# simple-board.net
KiCad netlist of a schematic drawn in EAGLE
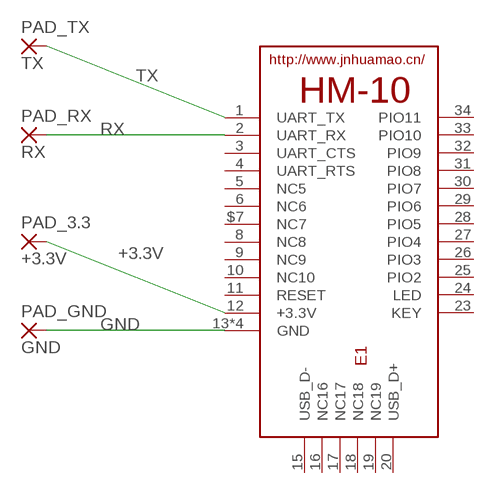
[diagram p0: schematic, sheet 1]

(export (version "E")
  (design (tool "Eeschema 10.0.6"))
  (components
    (comp (ref "E1")
      (value "HM-10-BOARD")
      (footprint "eagle-import:26.9X13X2.2_BOARD")
      (libsource (lib "eagle-import") (part "HM-10-BOARD"))
    )
    (comp (ref "PAD_3.3")
      (value "+3.3V")
      (footprint "eagle-import:1,6_0,8")
      (libsource (lib "eagle-import") (part "1,6/0,8"))
    )
    (comp (ref "PAD_GND")
      (value "GND")
      (footprint "eagle-import:1,6_0,8")
      (libsource (lib "eagle-import") (part "1,6/0,8"))
    )
    (comp (ref "PAD_RX")
      (value "RX")
      (footprint "eagle-import:1,6_0,8")
      (libsource (lib "eagle-import") (part "1,6/0,8"))
    )
    (comp (ref "PAD_TX")
      (value "TX")
      (footprint "eagle-import:1,6_0,8")
      (libsource (lib "eagle-import") (part "1,6/0,8"))
    )
  )
  (nets
    (net (code "1") (name "/+3.3V") (class "Default")
      (node (ref "E1") (pin "12") (pinfunction "+3.3V_12") (pintype "bidirectional"))
      (node (ref "PAD_3.3") (pin "1") (pinfunction "P_1") (pintype "passive"))
    )
    (net (code "2") (name "/GND") (class "Default")
      (node (ref "E1") (pin "13") (pinfunction "GND_13") (pintype "bidirectional"))
      (node (ref "E1") (pin "14") (pinfunction "GND_14") (pintype "bidirectional"))
      (node (ref "E1") (pin "21") (pinfunction "GND_21") (pintype "bidirectional"))
      (node (ref "E1") (pin "22") (pinfunction "GND_22") (pintype "bidirectional"))
      (node (ref "PAD_GND") (pin "1") (pinfunction "P_1") (pintype "passive"))
    )
    (net (code "3") (name "/RX") (class "Default")
      (node (ref "E1") (pin "2") (pinfunction "UART_RX_2") (pintype "bidirectional"))
      (node (ref "PAD_RX") (pin "1") (pinfunction "P_1") (pintype "passive"))
    )
    (net (code "4") (name "/TX") (class "Default")
      (node (ref "E1") (pin "1") (pinfunction "UART_TX_1") (pintype "bidirectional"))
      (node (ref "PAD_TX") (pin "1") (pinfunction "P_1") (pintype "passive"))
    )
    (net (code "5") (name "unconnected-(E1-KEY-Pad23)") (class "Default")
      (node (ref "E1") (pin "23") (pinfunction "KEY_23") (pintype "bidirectional"))
    )
    (net (code "6") (name "unconnected-(E1-LED-Pad24)") (class "Default")
      (node (ref "E1") (pin "24") (pinfunction "LED_24") (pintype "bidirectional"))
    )
    (net (code "7") (name "unconnected-(E1-NC5-Pad5)") (class "Default")
      (node (ref "E1") (pin "5") (pinfunction "NC5_5") (pintype "bidirectional"))
    )
    (net (code "8") (name "unconnected-(E1-NC6-Pad6)") (class "Default")
      (node (ref "E1") (pin "6") (pinfunction "NC6_6") (pintype "bidirectional"))
    )
    (net (code "9") (name "unconnected-(E1-NC7-Pad$7)") (class "Default")
      (node (ref "E1") (pin "$7") (pinfunction "NC7_$7") (pintype "bidirectional"))
    )
    (net (code "10") (name "unconnected-(E1-NC8-Pad8)") (class "Default")
      (node (ref "E1") (pin "8") (pinfunction "NC8_8") (pintype "bidirectional"))
    )
    (net (code "11") (name "unconnected-(E1-NC9-Pad9)") (class "Default")
      (node (ref "E1") (pin "9") (pinfunction "NC9_9") (pintype "bidirectional"))
    )
    (net (code "12") (name "unconnected-(E1-NC10-Pad10)") (class "Default")
      (node (ref "E1") (pin "10") (pinfunction "NC10_10") (pintype "bidirectional"))
    )
    (net (code "13") (name "unconnected-(E1-NC16-Pad16)") (class "Default")
      (node (ref "E1") (pin "16") (pinfunction "NC16_16") (pintype "bidirectional"))
    )
    (net (code "14") (name "unconnected-(E1-NC17-Pad17)") (class "Default")
      (node (ref "E1") (pin "17") (pinfunction "NC17_17") (pintype "bidirectional"))
    )
    (net (code "15") (name "unconnected-(E1-NC18-Pad18)") (class "Default")
      (node (ref "E1") (pin "18") (pinfunction "NC18_18") (pintype "bidirectional"))
    )
    (net (code "16") (name "unconnected-(E1-NC19-Pad19)") (class "Default")
      (node (ref "E1") (pin "19") (pinfunction "NC19_19") (pintype "bidirectional"))
    )
    (net (code "17") (name "unconnected-(E1-PIO2-Pad25)") (class "Default")
      (node (ref "E1") (pin "25") (pinfunction "PIO2_25") (pintype "bidirectional"))
    )
    (net (code "18") (name "unconnected-(E1-PIO3-Pad26)") (class "Default")
      (node (ref "E1") (pin "26") (pinfunction "PIO3_26") (pintype "bidirectional"))
    )
    (net (code "19") (name "unconnected-(E1-PIO4-Pad27)") (class "Default")
      (node (ref "E1") (pin "27") (pinfunction "PIO4_27") (pintype "bidirectional"))
    )
    (net (code "20") (name "unconnected-(E1-PIO5-Pad28)") (class "Default")
      (node (ref "E1") (pin "28") (pinfunction "PIO5_28") (pintype "bidirectional"))
    )
    (net (code "21") (name "unconnected-(E1-PIO6-Pad29)") (class "Default")
      (node (ref "E1") (pin "29") (pinfunction "PIO6_29") (pintype "bidirectional"))
    )
    (net (code "22") (name "unconnected-(E1-PIO7-Pad30)") (class "Default")
      (node (ref "E1") (pin "30") (pinfunction "PIO7_30") (pintype "bidirectional"))
    )
    (net (code "23") (name "unconnected-(E1-PIO8-Pad31)") (class "Default")
      (node (ref "E1") (pin "31") (pinfunction "PIO8_31") (pintype "bidirectional"))
    )
    (net (code "24") (name "unconnected-(E1-PIO9-Pad32)") (class "Default")
      (node (ref "E1") (pin "32") (pinfunction "PIO9_32") (pintype "bidirectional"))
    )
    (net (code "25") (name "unconnected-(E1-PIO10-Pad33)") (class "Default")
      (node (ref "E1") (pin "33") (pinfunction "PIO10_33") (pintype "bidirectional"))
    )
    (net (code "26") (name "unconnected-(E1-PIO11-Pad34)") (class "Default")
      (node (ref "E1") (pin "34") (pinfunction "PIO11_34") (pintype "bidirectional"))
    )
    (net (code "27") (name "unconnected-(E1-RESET-Pad11)") (class "Default")
      (node (ref "E1") (pin "11") (pinfunction "RESET_11") (pintype "bidirectional"))
    )
    (net (code "28") (name "unconnected-(E1-UART_CTS-Pad3)") (class "Default")
      (node (ref "E1") (pin "3") (pinfunction "UART_CTS_3") (pintype "bidirectional"))
    )
    (net (code "29") (name "unconnected-(E1-UART_RTS-Pad4)") (class "Default")
      (node (ref "E1") (pin "4") (pinfunction "UART_RTS_4") (pintype "bidirectional"))
    )
    (net (code "30") (name "unconnected-(E1-USB_D+-Pad20)") (class "Default")
      (node (ref "E1") (pin "20") (pinfunction "USB_D+_20") (pintype "bidirectional"))
    )
    (net (code "31") (name "unconnected-(E1-USB_D--Pad15)") (class "Default")
      (node (ref "E1") (pin "15") (pinfunction "USB_D-_15") (pintype "bidirectional"))
    )
  )
)
